# RJ45_EURORACK_BRIDGE_castellated.net
KiCad netlist of a schematic drawn in EAGLE
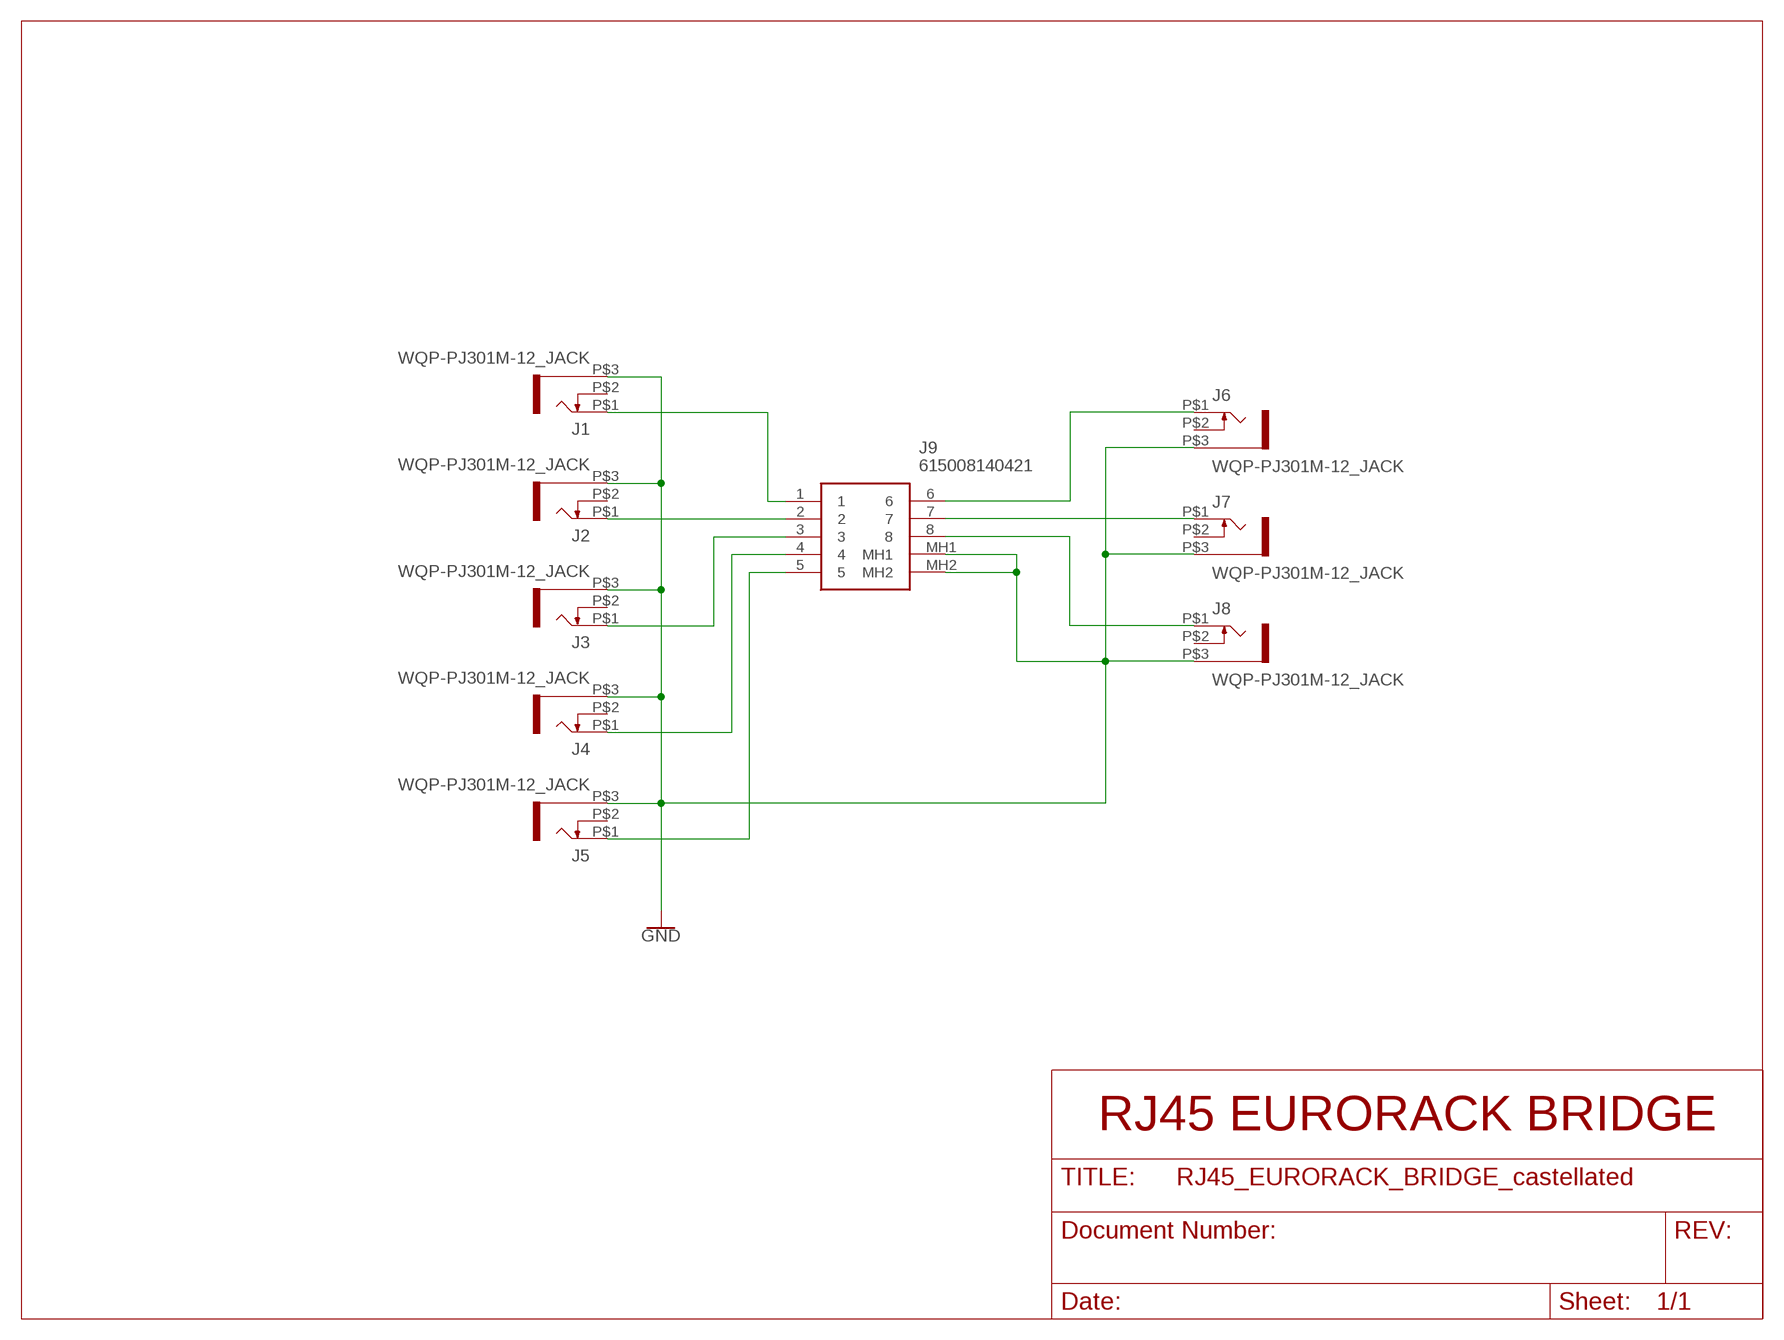
[diagram p0: schematic, sheet 1]

(export (version "E")
  (design (tool "Eeschema 10.0.6"))
  (components
    (comp (ref "J1")
      (value "WQP-PJ301M-12_JACK")
      (footprint "eagle-import:WQP-PJ301M-12_JACK")
      (libsource (lib "eagle-import") (part "WQP-PJ301M-12_JACK"))
    )
    (comp (ref "J2")
      (value "WQP-PJ301M-12_JACK")
      (footprint "eagle-import:WQP-PJ301M-12_JACK")
      (libsource (lib "eagle-import") (part "WQP-PJ301M-12_JACK"))
    )
    (comp (ref "J3")
      (value "WQP-PJ301M-12_JACK")
      (footprint "eagle-import:WQP-PJ301M-12_JACK")
      (libsource (lib "eagle-import") (part "WQP-PJ301M-12_JACK"))
    )
    (comp (ref "J4")
      (value "WQP-PJ301M-12_JACK")
      (footprint "eagle-import:WQP-PJ301M-12_JACK")
      (libsource (lib "eagle-import") (part "WQP-PJ301M-12_JACK"))
    )
    (comp (ref "J5")
      (value "WQP-PJ301M-12_JACK")
      (footprint "eagle-import:WQP-PJ301M-12_JACK")
      (libsource (lib "eagle-import") (part "WQP-PJ301M-12_JACK"))
    )
    (comp (ref "J6")
      (value "WQP-PJ301M-12_JACK")
      (footprint "eagle-import:WQP-PJ301M-12_JACK")
      (libsource (lib "eagle-import") (part "WQP-PJ301M-12_JACK"))
    )
    (comp (ref "J7")
      (value "WQP-PJ301M-12_JACK")
      (footprint "eagle-import:WQP-PJ301M-12_JACK")
      (libsource (lib "eagle-import") (part "WQP-PJ301M-12_JACK"))
    )
    (comp (ref "J8")
      (value "WQP-PJ301M-12_JACK")
      (footprint "eagle-import:WQP-PJ301M-12_JACK")
      (libsource (lib "eagle-import") (part "WQP-PJ301M-12_JACK"))
    )
    (comp (ref "J9")
      (value "615008140421")
      (footprint "eagle-import:615008140421")
      (fields (field (name "MOUSER_PART_NUMBER") "710-615008140421"))
      (libsource (lib "eagle-import") (part "615008140421"))
    )
  )
  (nets
    (net (code "1") (name "GND") (class "Default")
      (node (ref "J1") (pin "P$3") (pinfunction "1_P$3") (pintype "passive"))
      (node (ref "J2") (pin "P$3") (pinfunction "1_P$3") (pintype "passive"))
      (node (ref "J3") (pin "P$3") (pinfunction "1_P$3") (pintype "passive"))
      (node (ref "J4") (pin "P$3") (pinfunction "1_P$3") (pintype "passive"))
      (node (ref "J5") (pin "P$3") (pinfunction "1_P$3") (pintype "passive"))
      (node (ref "J6") (pin "P$3") (pinfunction "1_P$3") (pintype "passive"))
      (node (ref "J7") (pin "P$3") (pinfunction "1_P$3") (pintype "passive"))
      (node (ref "J8") (pin "P$3") (pinfunction "1_P$3") (pintype "passive"))
      (node (ref "J9") (pin "MH1") (pinfunction "MH1_MH1") (pintype "bidirectional"))
      (node (ref "J9") (pin "MH2") (pinfunction "MH2_MH2") (pintype "bidirectional"))
    )
    (net (code "2") (name "Net-(J1-2)") (class "Default")
      (node (ref "J1") (pin "P$1") (pinfunction "2_P$1") (pintype "passive"))
      (node (ref "J9") (pin "1") (pinfunction "1_1") (pintype "bidirectional"))
    )
    (net (code "3") (name "Net-(J2-2)") (class "Default")
      (node (ref "J2") (pin "P$1") (pinfunction "2_P$1") (pintype "passive"))
      (node (ref "J9") (pin "2") (pinfunction "2_2") (pintype "bidirectional"))
    )
    (net (code "4") (name "Net-(J3-2)") (class "Default")
      (node (ref "J3") (pin "P$1") (pinfunction "2_P$1") (pintype "passive"))
      (node (ref "J9") (pin "3") (pinfunction "3_3") (pintype "bidirectional"))
    )
    (net (code "5") (name "Net-(J4-2)") (class "Default")
      (node (ref "J4") (pin "P$1") (pinfunction "2_P$1") (pintype "passive"))
      (node (ref "J9") (pin "4") (pinfunction "4_4") (pintype "bidirectional"))
    )
    (net (code "6") (name "Net-(J5-2)") (class "Default")
      (node (ref "J5") (pin "P$1") (pinfunction "2_P$1") (pintype "passive"))
      (node (ref "J9") (pin "5") (pinfunction "5_5") (pintype "bidirectional"))
    )
    (net (code "7") (name "Net-(J6-2)") (class "Default")
      (node (ref "J6") (pin "P$1") (pinfunction "2_P$1") (pintype "passive"))
      (node (ref "J9") (pin "6") (pinfunction "6_6") (pintype "bidirectional"))
    )
    (net (code "8") (name "Net-(J7-2)") (class "Default")
      (node (ref "J7") (pin "P$1") (pinfunction "2_P$1") (pintype "passive"))
      (node (ref "J9") (pin "7") (pinfunction "7_7") (pintype "bidirectional"))
    )
    (net (code "9") (name "Net-(J8-2)") (class "Default")
      (node (ref "J8") (pin "P$1") (pinfunction "2_P$1") (pintype "passive"))
      (node (ref "J9") (pin "8") (pinfunction "8_8") (pintype "bidirectional"))
    )
    (net (code "10") (name "unconnected-(J1-3-PadP$2)") (class "Default")
      (node (ref "J1") (pin "P$2") (pinfunction "3_P$2") (pintype "passive"))
    )
    (net (code "11") (name "unconnected-(J2-3-PadP$2)") (class "Default")
      (node (ref "J2") (pin "P$2") (pinfunction "3_P$2") (pintype "passive"))
    )
    (net (code "12") (name "unconnected-(J3-3-PadP$2)") (class "Default")
      (node (ref "J3") (pin "P$2") (pinfunction "3_P$2") (pintype "passive"))
    )
    (net (code "13") (name "unconnected-(J4-3-PadP$2)") (class "Default")
      (node (ref "J4") (pin "P$2") (pinfunction "3_P$2") (pintype "passive"))
    )
    (net (code "14") (name "unconnected-(J5-3-PadP$2)") (class "Default")
      (node (ref "J5") (pin "P$2") (pinfunction "3_P$2") (pintype "passive"))
    )
    (net (code "15") (name "unconnected-(J6-3-PadP$2)") (class "Default")
      (node (ref "J6") (pin "P$2") (pinfunction "3_P$2") (pintype "passive"))
    )
    (net (code "16") (name "unconnected-(J7-3-PadP$2)") (class "Default")
      (node (ref "J7") (pin "P$2") (pinfunction "3_P$2") (pintype "passive"))
    )
    (net (code "17") (name "unconnected-(J8-3-PadP$2)") (class "Default")
      (node (ref "J8") (pin "P$2") (pinfunction "3_P$2") (pintype "passive"))
    )
  )
)
